# GPIO_Block.net
KiCad netlist of a schematic drawn in EAGLE
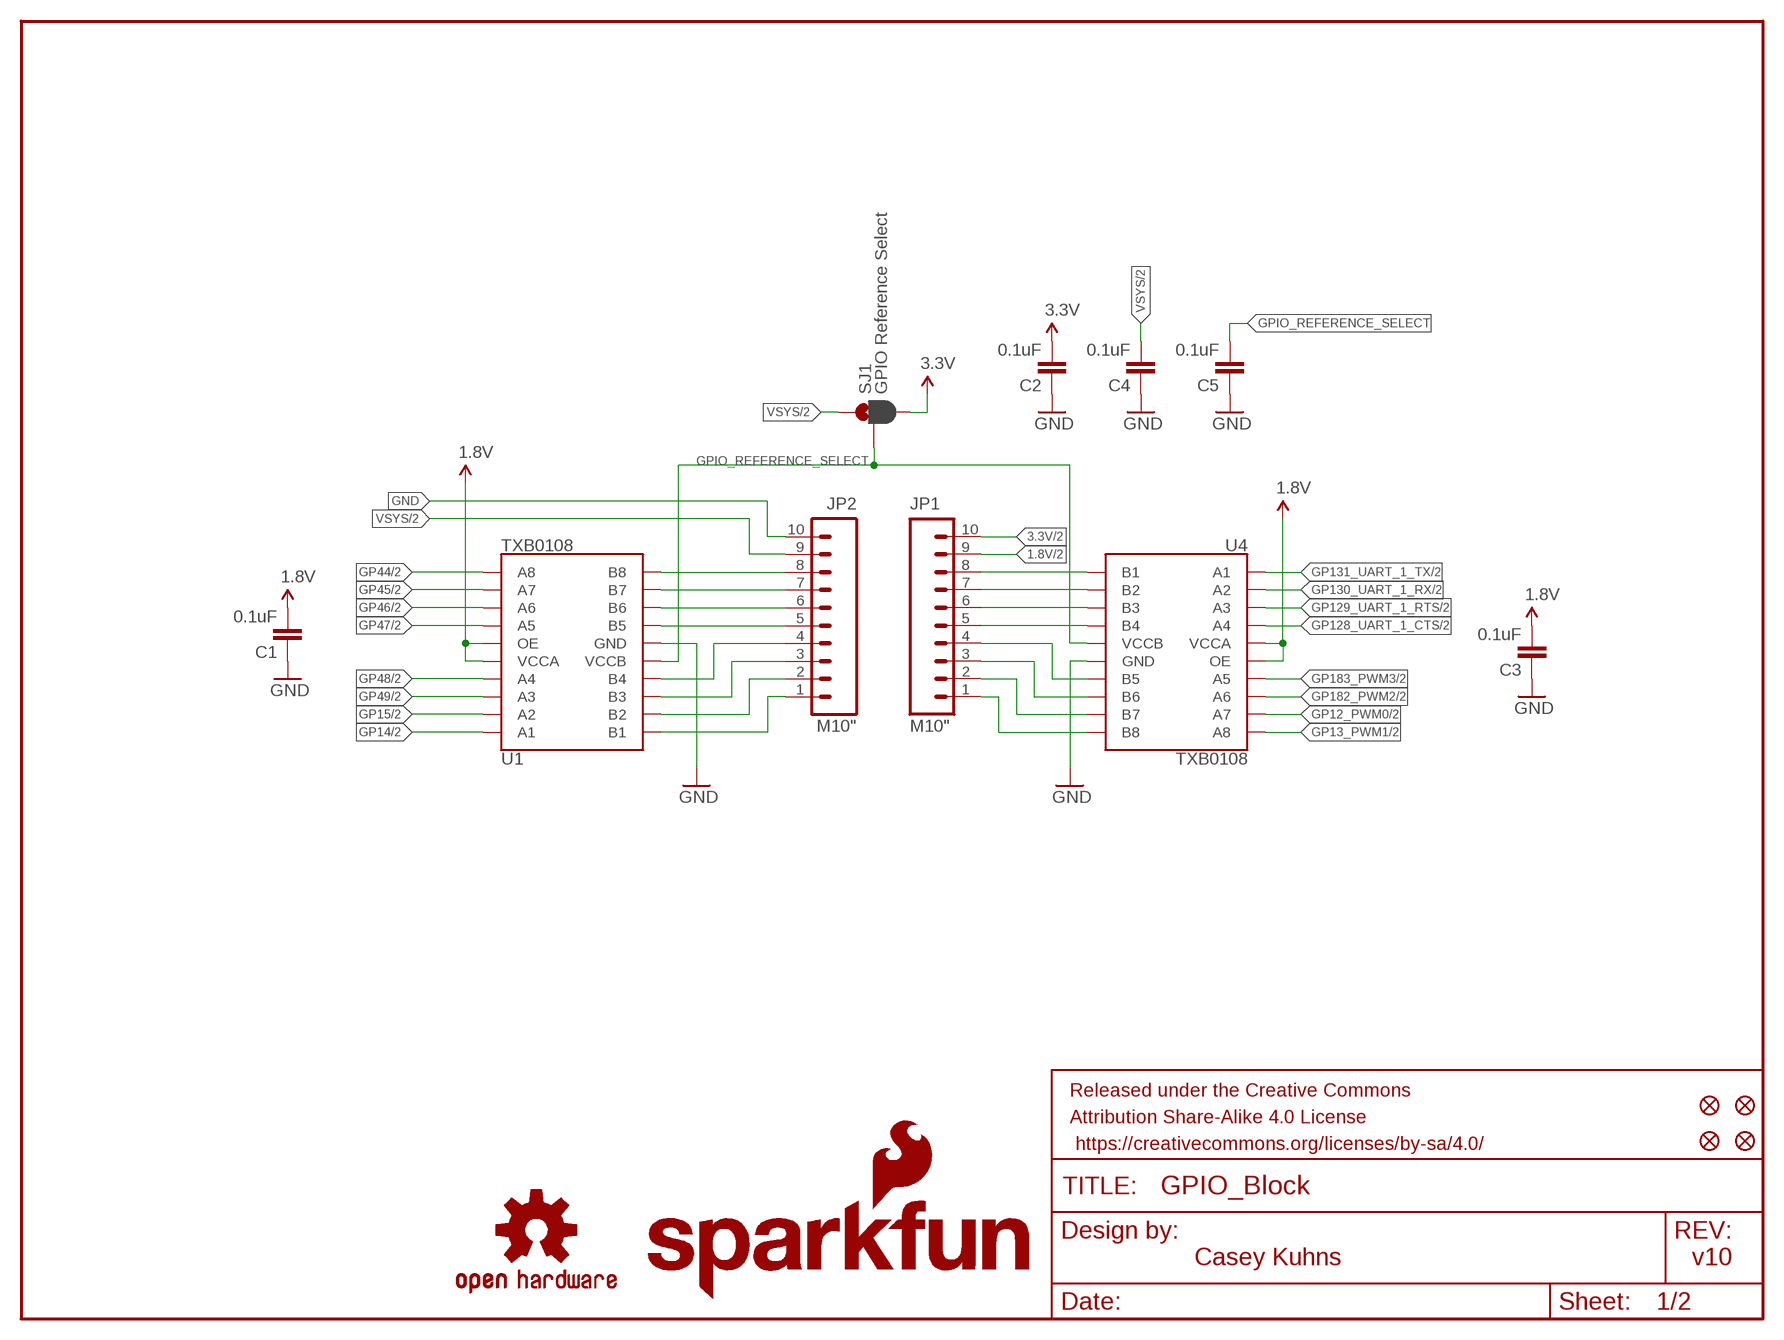
[diagram p0: schematic, sheet 1]
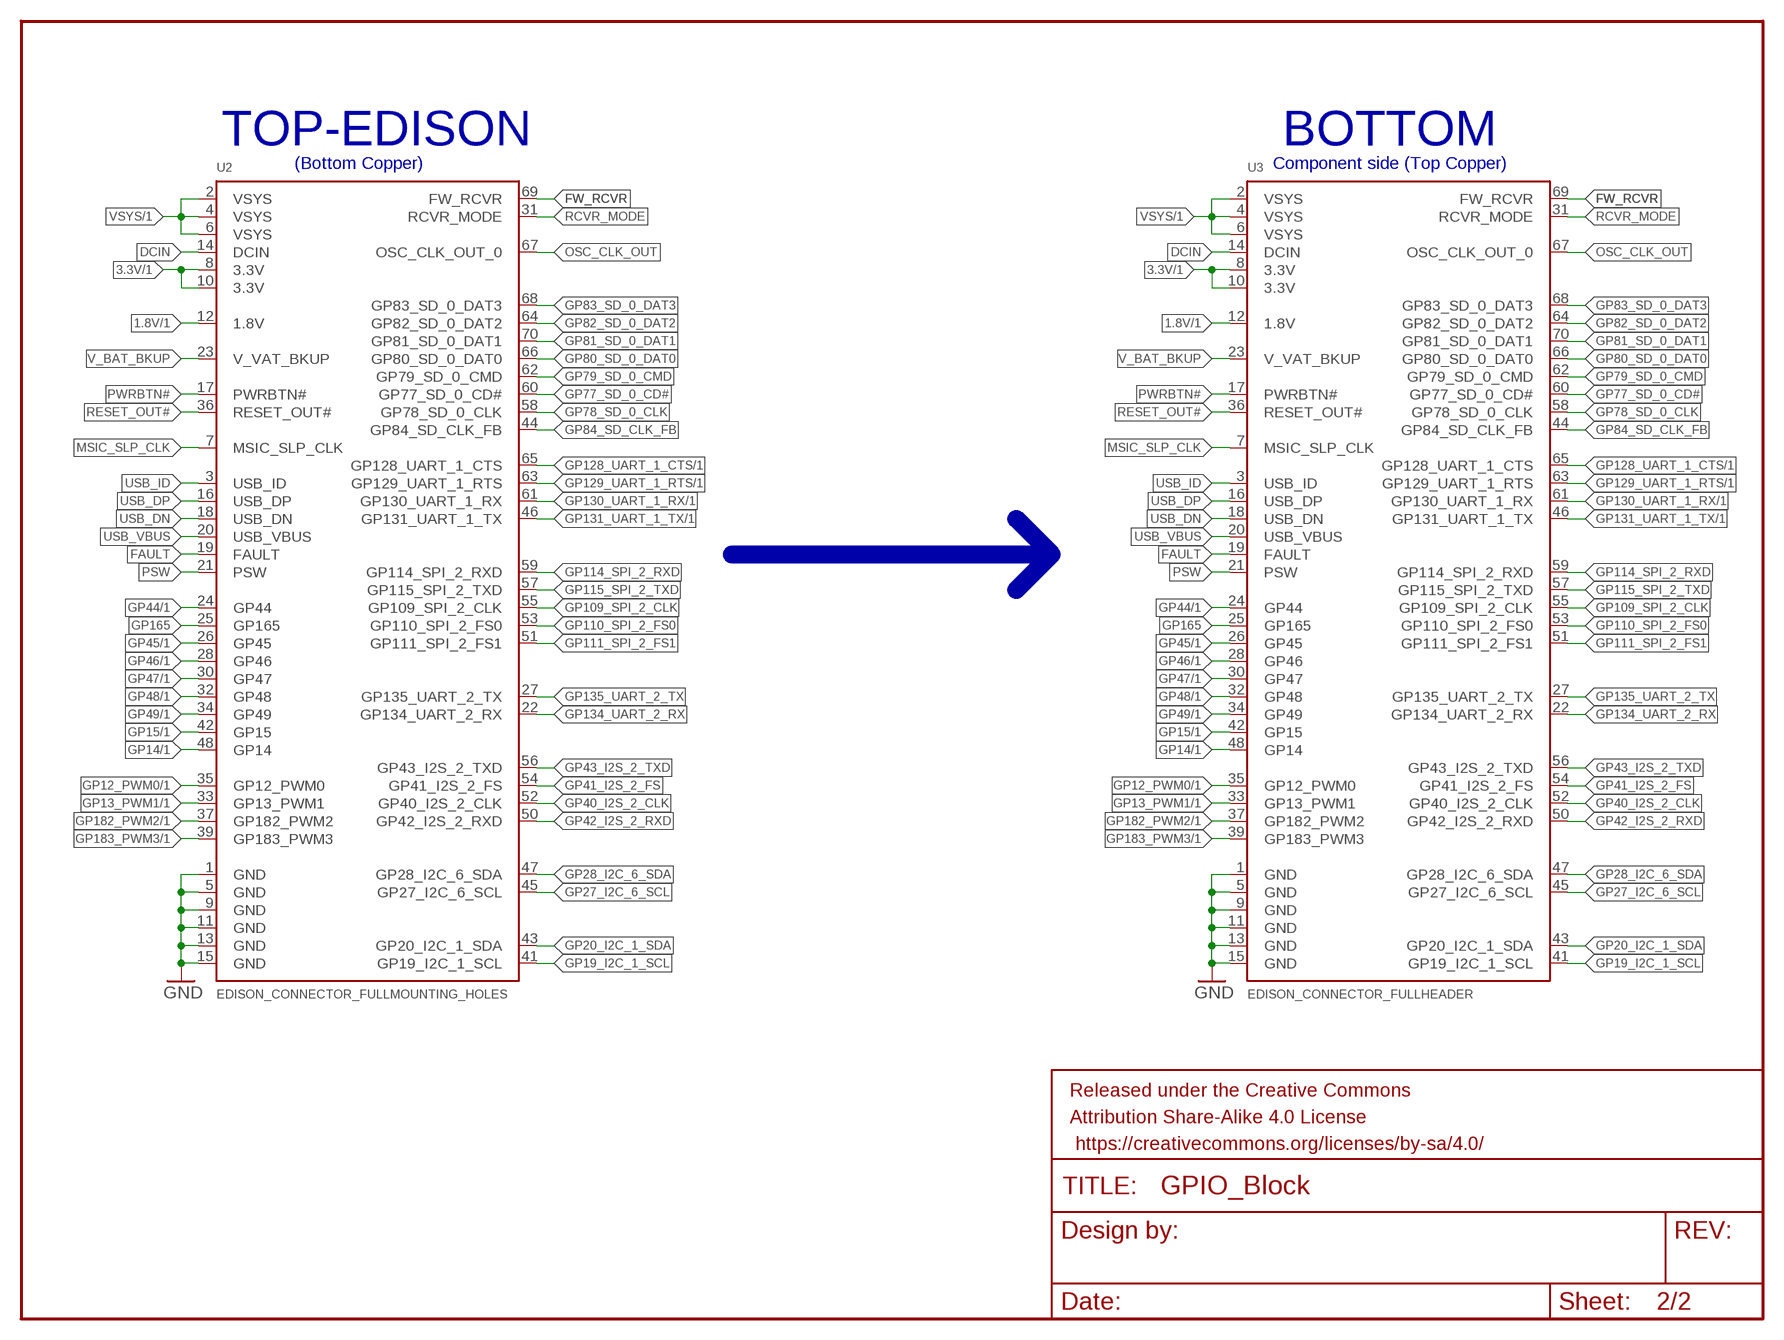
[diagram p1: schematic, sheet 2]

(export (version "E")
  (design (tool "Eeschema 10.0.6"))
  (components
    (comp (ref "C1")
      (value "0.1uF")
      (footprint "eagle-import:0603-CAP")
      (libsource (lib "eagle-import") (part "0.1UF-25V(+80/-20%)(0603)"))
    )
    (comp (ref "C2")
      (value "0.1uF")
      (footprint "eagle-import:0603-CAP")
      (libsource (lib "eagle-import") (part "0.1UF-25V(+80/-20%)(0603)"))
    )
    (comp (ref "C3")
      (value "0.1uF")
      (footprint "eagle-import:0603-CAP")
      (libsource (lib "eagle-import") (part "0.1UF-25V(+80/-20%)(0603)"))
    )
    (comp (ref "C4")
      (value "0.1uF")
      (footprint "eagle-import:0603-CAP")
      (libsource (lib "eagle-import") (part "0.1UF-25V(+80/-20%)(0603)"))
    )
    (comp (ref "C5")
      (value "0.1uF")
      (footprint "eagle-import:0603-CAP")
      (libsource (lib "eagle-import") (part "0.1UF-25V(+80/-20%)(0603)"))
    )
    (comp (ref "FID1")
      (value "FIDUCIAL1X2")
      (footprint "eagle-import:FIDUCIAL-1X2")
      (libsource (lib "eagle-import") (part "FIDUCIAL1X2"))
    )
    (comp (ref "FID2")
      (value "FIDUCIAL1X2")
      (footprint "eagle-import:FIDUCIAL-1X2")
      (libsource (lib "eagle-import") (part "FIDUCIAL1X2"))
    )
    (comp (ref "FID3")
      (value "FIDUCIAL1X2")
      (footprint "eagle-import:FIDUCIAL-1X2")
      (libsource (lib "eagle-import") (part "FIDUCIAL1X2"))
    )
    (comp (ref "FID4")
      (value "FIDUCIAL1X2")
      (footprint "eagle-import:FIDUCIAL-1X2")
      (libsource (lib "eagle-import") (part "FIDUCIAL1X2"))
    )
    (comp (ref "FRAME1")
      (value "FRAME-LETTER")
      (footprint "eagle-import:CREATIVE_COMMONS")
      (libsource (lib "eagle-import") (part "FRAME-LETTER"))
    )
    (comp (ref "JP1")
      (value "M10\"")
      (footprint "eagle-import:1X10")
      (libsource (lib "eagle-import") (part "M10{dblquote}"))
    )
    (comp (ref "JP2")
      (value "M10\"")
      (footprint "eagle-import:1X10")
      (libsource (lib "eagle-import") (part "M10{dblquote}"))
    )
    (comp (ref "LOGO1")
      (value "OSHW-LOGOS")
      (footprint "eagle-import:OSHW-LOGO-S")
      (libsource (lib "eagle-import") (part "OSHW-LOGOS"))
    )
    (comp (ref "LOGO4")
      (value "SFE_LOGO_NAME_FLAME.1_INCH")
      (footprint "eagle-import:SFE_LOGO_NAME_FLAME_.1")
      (libsource (lib "eagle-import") (part "SFE_LOGO_NAME_FLAME.1_INCH"))
    )
    (comp (ref "SJ1")
      (value "GPIO Reference Select")
      (footprint "eagle-import:PAD-JUMPER-3-2OF3_NC_BY_PASTE_YES_SILK_FULL_BOX")
      (libsource (lib "eagle-import") (part "JUMPER-PAD-3-2OF3_NC_BY_PASTE"))
    )
    (comp (ref "U1")
      (value "TXB0108")
      (footprint "eagle-import:UFDFN-20")
      (libsource (lib "eagle-import") (part "TXB0108"))
    )
    (comp (ref "U4")
      (value "TXB0108")
      (footprint "eagle-import:UFDFN-20")
      (libsource (lib "eagle-import") (part "TXB0108"))
    )
    (comp (ref "FRAME2")
      (value "FRAME-LETTER")
      (footprint "eagle-import:CREATIVE_COMMONS")
      (libsource (lib "eagle-import") (part "FRAME-LETTER"))
    )
    (comp (ref "U2")
      (value "EDISON_CONNECTOR_FULLMOUNTING_HOLES")
      (footprint "eagle-import:EDISON_DAUGHTER")
      (libsource (lib "eagle-import") (part "EDISON_CONNECTOR_FULLMOUNTING_HOLES"))
    )
    (comp (ref "U3")
      (value "EDISON_CONNECTOR_FULLHEADER")
      (footprint "eagle-import:DF40C-70DP-0.4(51)")
      (libsource (lib "eagle-import") (part "EDISON_CONNECTOR_FULLHEADER"))
    )
  )
  (nets
    (net (code "1") (name "1.8V") (class "Default")
      (node (ref "C1") (pin "2") (pinfunction "2_2") (pintype "passive"))
      (node (ref "C3") (pin "2") (pinfunction "2_2") (pintype "passive"))
      (node (ref "JP1") (pin "9") (pinfunction "9_9") (pintype "passive"))
      (node (ref "U1") (pin "5") (pinfunction "VCCA_5") (pintype "bidirectional"))
      (node (ref "U1") (pin "6") (pinfunction "OE_6") (pintype "bidirectional"))
      (node (ref "U2") (pin "12") (pinfunction "1.8V_12") (pintype "bidirectional"))
      (node (ref "U3") (pin "12") (pinfunction "1.8V_12") (pintype "bidirectional"))
      (node (ref "U4") (pin "5") (pinfunction "VCCA_5") (pintype "bidirectional"))
      (node (ref "U4") (pin "6") (pinfunction "OE_6") (pintype "bidirectional"))
    )
    (net (code "2") (name "3.3V") (class "Default")
      (node (ref "C2") (pin "2") (pinfunction "2_2") (pintype "passive"))
      (node (ref "JP1") (pin "10") (pinfunction "10_10") (pintype "passive"))
      (node (ref "SJ1") (pin "3") (pinfunction "3_3") (pintype "passive"))
      (node (ref "U2") (pin "10") (pinfunction "3.3V_10") (pintype "bidirectional"))
      (node (ref "U2") (pin "8") (pinfunction "3.3V_8") (pintype "bidirectional"))
      (node (ref "U3") (pin "10") (pinfunction "3.3V_10") (pintype "bidirectional"))
      (node (ref "U3") (pin "8") (pinfunction "3.3V_8") (pintype "bidirectional"))
    )
    (net (code "3") (name "DCIN") (class "Default")
      (node (ref "U2") (pin "14") (pinfunction "DCIN_14") (pintype "bidirectional"))
      (node (ref "U3") (pin "14") (pinfunction "DCIN_14") (pintype "bidirectional"))
    )
    (net (code "4") (name "FAULT") (class "Default")
      (node (ref "U2") (pin "19") (pinfunction "FAULT_19") (pintype "bidirectional"))
      (node (ref "U3") (pin "19") (pinfunction "FAULT_19") (pintype "bidirectional"))
    )
    (net (code "5") (name "FW_RCVR") (class "Default")
      (node (ref "U2") (pin "69") (pinfunction "FW_RCVR_69") (pintype "bidirectional"))
      (node (ref "U3") (pin "69") (pinfunction "FW_RCVR_69") (pintype "bidirectional"))
    )
    (net (code "6") (name "GND") (class "Default")
      (node (ref "C1") (pin "1") (pinfunction "1_1") (pintype "passive"))
      (node (ref "C2") (pin "1") (pinfunction "1_1") (pintype "passive"))
      (node (ref "C3") (pin "1") (pinfunction "1_1") (pintype "passive"))
      (node (ref "C4") (pin "1") (pinfunction "1_1") (pintype "passive"))
      (node (ref "C5") (pin "1") (pinfunction "1_1") (pintype "passive"))
      (node (ref "JP2") (pin "10") (pinfunction "10_10") (pintype "passive"))
      (node (ref "U1") (pin "15") (pinfunction "GND_15") (pintype "bidirectional"))
      (node (ref "U2") (pin "1") (pinfunction "GND_1") (pintype "bidirectional"))
      (node (ref "U2") (pin "11") (pinfunction "GND_11") (pintype "bidirectional"))
      (node (ref "U2") (pin "13") (pinfunction "GND_13") (pintype "bidirectional"))
      (node (ref "U2") (pin "15") (pinfunction "GND_15") (pintype "bidirectional"))
      (node (ref "U2") (pin "5") (pinfunction "GND_5") (pintype "bidirectional"))
      (node (ref "U2") (pin "9") (pinfunction "GND_9") (pintype "bidirectional"))
      (node (ref "U3") (pin "1") (pinfunction "GND_1") (pintype "bidirectional"))
      (node (ref "U3") (pin "11") (pinfunction "GND_11") (pintype "bidirectional"))
      (node (ref "U3") (pin "13") (pinfunction "GND_13") (pintype "bidirectional"))
      (node (ref "U3") (pin "15") (pinfunction "GND_15") (pintype "bidirectional"))
      (node (ref "U3") (pin "5") (pinfunction "GND_5") (pintype "bidirectional"))
      (node (ref "U3") (pin "9") (pinfunction "GND_9") (pintype "bidirectional"))
      (node (ref "U4") (pin "15") (pinfunction "GND_15") (pintype "bidirectional"))
    )
    (net (code "7") (name "GP12_PWM0") (class "Default")
      (node (ref "U2") (pin "35") (pinfunction "GP12_PWM0_35") (pintype "bidirectional"))
      (node (ref "U3") (pin "35") (pinfunction "GP12_PWM0_35") (pintype "bidirectional"))
      (node (ref "U4") (pin "9") (pinfunction "A7_9") (pintype "bidirectional"))
    )
    (net (code "8") (name "GP13_PWM1") (class "Default")
      (node (ref "U2") (pin "33") (pinfunction "GP13_PWM1_33") (pintype "bidirectional"))
      (node (ref "U3") (pin "33") (pinfunction "GP13_PWM1_33") (pintype "bidirectional"))
      (node (ref "U4") (pin "10") (pinfunction "A8_10") (pintype "bidirectional"))
    )
    (net (code "9") (name "GP14") (class "Default")
      (node (ref "U1") (pin "1") (pinfunction "A1_1") (pintype "bidirectional"))
      (node (ref "U2") (pin "48") (pinfunction "GP14_48") (pintype "bidirectional"))
      (node (ref "U3") (pin "48") (pinfunction "GP14_48") (pintype "bidirectional"))
    )
    (net (code "10") (name "GP15") (class "Default")
      (node (ref "U1") (pin "2") (pinfunction "A2_2") (pintype "bidirectional"))
      (node (ref "U2") (pin "42") (pinfunction "GP15_42") (pintype "bidirectional"))
      (node (ref "U3") (pin "42") (pinfunction "GP15_42") (pintype "bidirectional"))
    )
    (net (code "11") (name "GP19_I2C_1_SCL") (class "Default")
      (node (ref "U2") (pin "41") (pinfunction "GP19_I2C_1_SCL_41") (pintype "bidirectional"))
      (node (ref "U3") (pin "41") (pinfunction "GP19_I2C_1_SCL_41") (pintype "bidirectional"))
    )
    (net (code "12") (name "GP20_I2C_1_SDA") (class "Default")
      (node (ref "U2") (pin "43") (pinfunction "GP20_I2C_1_SDA_43") (pintype "bidirectional"))
      (node (ref "U3") (pin "43") (pinfunction "GP20_I2C_1_SDA_43") (pintype "bidirectional"))
    )
    (net (code "13") (name "GP27_I2C_6_SCL") (class "Default")
      (node (ref "U2") (pin "45") (pinfunction "GP27_I2C_6_SCL_45") (pintype "bidirectional"))
      (node (ref "U3") (pin "45") (pinfunction "GP27_I2C_6_SCL_45") (pintype "bidirectional"))
    )
    (net (code "14") (name "GP28_I2C_6_SDA") (class "Default")
      (node (ref "U2") (pin "47") (pinfunction "GP28_I2C_6_SDA_47") (pintype "bidirectional"))
      (node (ref "U3") (pin "47") (pinfunction "GP28_I2C_6_SDA_47") (pintype "bidirectional"))
    )
    (net (code "15") (name "GP40_I2S_2_CLK") (class "Default")
      (node (ref "U2") (pin "52") (pinfunction "GP40_I2S_2_CLK_52") (pintype "bidirectional"))
      (node (ref "U3") (pin "52") (pinfunction "GP40_I2S_2_CLK_52") (pintype "bidirectional"))
    )
    (net (code "16") (name "GP41_I2S_2_FS") (class "Default")
      (node (ref "U2") (pin "54") (pinfunction "GP41_I2S_2_FS_54") (pintype "bidirectional"))
      (node (ref "U3") (pin "54") (pinfunction "GP41_I2S_2_FS_54") (pintype "bidirectional"))
    )
    (net (code "17") (name "GP42_I2S_2_RXD") (class "Default")
      (node (ref "U2") (pin "50") (pinfunction "GP42_I2S_2_RXD_50") (pintype "bidirectional"))
      (node (ref "U3") (pin "50") (pinfunction "GP42_I2S_2_RXD_50") (pintype "bidirectional"))
    )
    (net (code "18") (name "GP43_I2S_2_TXD") (class "Default")
      (node (ref "U2") (pin "56") (pinfunction "GP43_I2S_2_TXD_56") (pintype "bidirectional"))
      (node (ref "U3") (pin "56") (pinfunction "GP43_I2S_2_TXD_56") (pintype "bidirectional"))
    )
    (net (code "19") (name "GP44") (class "Default")
      (node (ref "U1") (pin "10") (pinfunction "A8_10") (pintype "bidirectional"))
      (node (ref "U2") (pin "24") (pinfunction "GP44_24") (pintype "bidirectional"))
      (node (ref "U3") (pin "24") (pinfunction "GP44_24") (pintype "bidirectional"))
    )
    (net (code "20") (name "GP45") (class "Default")
      (node (ref "U1") (pin "9") (pinfunction "A7_9") (pintype "bidirectional"))
      (node (ref "U2") (pin "26") (pinfunction "GP45_26") (pintype "bidirectional"))
      (node (ref "U3") (pin "26") (pinfunction "GP45_26") (pintype "bidirectional"))
    )
    (net (code "21") (name "GP46") (class "Default")
      (node (ref "U1") (pin "8") (pinfunction "A6_8") (pintype "bidirectional"))
      (node (ref "U2") (pin "28") (pinfunction "GP46_28") (pintype "bidirectional"))
      (node (ref "U3") (pin "28") (pinfunction "GP46_28") (pintype "bidirectional"))
    )
    (net (code "22") (name "GP47") (class "Default")
      (node (ref "U1") (pin "7") (pinfunction "A5_7") (pintype "bidirectional"))
      (node (ref "U2") (pin "30") (pinfunction "GP47_30") (pintype "bidirectional"))
      (node (ref "U3") (pin "30") (pinfunction "GP47_30") (pintype "bidirectional"))
    )
    (net (code "23") (name "GP48") (class "Default")
      (node (ref "U1") (pin "4") (pinfunction "A4_4") (pintype "bidirectional"))
      (node (ref "U2") (pin "32") (pinfunction "GP48_32") (pintype "bidirectional"))
      (node (ref "U3") (pin "32") (pinfunction "GP48_32") (pintype "bidirectional"))
    )
    (net (code "24") (name "GP49") (class "Default")
      (node (ref "U1") (pin "3") (pinfunction "A3_3") (pintype "bidirectional"))
      (node (ref "U2") (pin "34") (pinfunction "GP49_34") (pintype "bidirectional"))
      (node (ref "U3") (pin "34") (pinfunction "GP49_34") (pintype "bidirectional"))
    )
    (net (code "25") (name "GP77_SD_0_CD#") (class "Default")
      (node (ref "U2") (pin "60") (pinfunction "GP77_SD_0_CD#_60") (pintype "bidirectional"))
      (node (ref "U3") (pin "60") (pinfunction "GP77_SD_0_CD#_60") (pintype "bidirectional"))
    )
    (net (code "26") (name "GP78_SD_0_CLK") (class "Default")
      (node (ref "U2") (pin "58") (pinfunction "GP78_SD_0_CLK_58") (pintype "bidirectional"))
      (node (ref "U3") (pin "58") (pinfunction "GP78_SD_0_CLK_58") (pintype "bidirectional"))
    )
    (net (code "27") (name "GP79_SD_0_CMD") (class "Default")
      (node (ref "U2") (pin "62") (pinfunction "GP79_SD_0_CMD_62") (pintype "bidirectional"))
      (node (ref "U3") (pin "62") (pinfunction "GP79_SD_0_CMD_62") (pintype "bidirectional"))
    )
    (net (code "28") (name "GP80_SD_0_DAT0") (class "Default")
      (node (ref "U2") (pin "66") (pinfunction "GP80_SD_0_DAT0_66") (pintype "bidirectional"))
      (node (ref "U3") (pin "66") (pinfunction "GP80_SD_0_DAT0_66") (pintype "bidirectional"))
    )
    (net (code "29") (name "GP81_SD_0_DAT1") (class "Default")
      (node (ref "U2") (pin "70") (pinfunction "GP81_SD_0_DAT1_70") (pintype "bidirectional"))
      (node (ref "U3") (pin "70") (pinfunction "GP81_SD_0_DAT1_70") (pintype "bidirectional"))
    )
    (net (code "30") (name "GP82_SD_0_DAT2") (class "Default")
      (node (ref "U2") (pin "64") (pinfunction "GP82_SD_0_DAT2_64") (pintype "bidirectional"))
      (node (ref "U3") (pin "64") (pinfunction "GP82_SD_0_DAT2_64") (pintype "bidirectional"))
    )
    (net (code "31") (name "GP83_SD_0_DAT3") (class "Default")
      (node (ref "U2") (pin "68") (pinfunction "GP83_SD_0_DAT3_68") (pintype "bidirectional"))
      (node (ref "U3") (pin "68") (pinfunction "GP83_SD_0_DAT3_68") (pintype "bidirectional"))
    )
    (net (code "32") (name "GP84_SD_CLK_FB") (class "Default")
      (node (ref "U2") (pin "44") (pinfunction "GP84_SD_CLK_FB_44") (pintype "bidirectional"))
      (node (ref "U3") (pin "44") (pinfunction "GP84_SD_CLK_FB_44") (pintype "bidirectional"))
    )
    (net (code "33") (name "GP109_SPI_2_CLK") (class "Default")
      (node (ref "U2") (pin "55") (pinfunction "GP109_SPI_2_CLK_55") (pintype "bidirectional"))
      (node (ref "U3") (pin "55") (pinfunction "GP109_SPI_2_CLK_55") (pintype "bidirectional"))
    )
    (net (code "34") (name "GP110_SPI_2_FS0") (class "Default")
      (node (ref "U2") (pin "53") (pinfunction "GP110_SPI_2_FS0_53") (pintype "bidirectional"))
      (node (ref "U3") (pin "53") (pinfunction "GP110_SPI_2_FS0_53") (pintype "bidirectional"))
    )
    (net (code "35") (name "GP111_SPI_2_FS1") (class "Default")
      (node (ref "U2") (pin "51") (pinfunction "GP111_SPI_2_FS1_51") (pintype "bidirectional"))
      (node (ref "U3") (pin "51") (pinfunction "GP111_SPI_2_FS1_51") (pintype "bidirectional"))
    )
    (net (code "36") (name "GP114_SPI_2_RXD") (class "Default")
      (node (ref "U2") (pin "59") (pinfunction "GP114_SPI_2_RXD_59") (pintype "bidirectional"))
      (node (ref "U3") (pin "59") (pinfunction "GP114_SPI_2_RXD_59") (pintype "bidirectional"))
    )
    (net (code "37") (name "GP115_SPI_2_TXD") (class "Default")
      (node (ref "U2") (pin "57") (pinfunction "GP115_SPI_2_TXD_57") (pintype "bidirectional"))
      (node (ref "U3") (pin "57") (pinfunction "GP115_SPI_2_TXD_57") (pintype "bidirectional"))
    )
    (net (code "38") (name "GP128_UART_1_CTS") (class "Default")
      (node (ref "U2") (pin "65") (pinfunction "GP128_UART_1_CTS_65") (pintype "bidirectional"))
      (node (ref "U3") (pin "65") (pinfunction "GP128_UART_1_CTS_65") (pintype "bidirectional"))
      (node (ref "U4") (pin "4") (pinfunction "A4_4") (pintype "bidirectional"))
    )
    (net (code "39") (name "GP129_UART_1_RTS") (class "Default")
      (node (ref "U2") (pin "63") (pinfunction "GP129_UART_1_RTS_63") (pintype "bidirectional"))
      (node (ref "U3") (pin "63") (pinfunction "GP129_UART_1_RTS_63") (pintype "bidirectional"))
      (node (ref "U4") (pin "3") (pinfunction "A3_3") (pintype "bidirectional"))
    )
    (net (code "40") (name "GP130_UART_1_RX") (class "Default")
      (node (ref "U2") (pin "61") (pinfunction "GP130_UART_1_RX_61") (pintype "bidirectional"))
      (node (ref "U3") (pin "61") (pinfunction "GP130_UART_1_RX_61") (pintype "bidirectional"))
      (node (ref "U4") (pin "2") (pinfunction "A2_2") (pintype "bidirectional"))
    )
    (net (code "41") (name "GP131_UART_1_TX") (class "Default")
      (node (ref "U2") (pin "46") (pinfunction "GP131_UART_1_TX_46") (pintype "bidirectional"))
      (node (ref "U3") (pin "46") (pinfunction "GP131_UART_1_TX_46") (pintype "bidirectional"))
      (node (ref "U4") (pin "1") (pinfunction "A1_1") (pintype "bidirectional"))
    )
    (net (code "42") (name "GP134_UART_2_RX") (class "Default")
      (node (ref "U2") (pin "22") (pinfunction "GP134_UART_2_RX_22") (pintype "bidirectional"))
      (node (ref "U3") (pin "22") (pinfunction "GP134_UART_2_RX_22") (pintype "bidirectional"))
    )
    (net (code "43") (name "GP135_UART_2_TX") (class "Default")
      (node (ref "U2") (pin "27") (pinfunction "GP135_UART_2_TX_27") (pintype "bidirectional"))
      (node (ref "U3") (pin "27") (pinfunction "GP135_UART_2_TX_27") (pintype "bidirectional"))
    )
    (net (code "44") (name "GP165") (class "Default")
      (node (ref "U2") (pin "25") (pinfunction "GP165_25") (pintype "bidirectional"))
      (node (ref "U3") (pin "25") (pinfunction "GP165_25") (pintype "bidirectional"))
    )
    (net (code "45") (name "GP182_PWM2") (class "Default")
      (node (ref "U2") (pin "37") (pinfunction "GP182_PWM2_37") (pintype "bidirectional"))
      (node (ref "U3") (pin "37") (pinfunction "GP182_PWM2_37") (pintype "bidirectional"))
      (node (ref "U4") (pin "8") (pinfunction "A6_8") (pintype "bidirectional"))
    )
    (net (code "46") (name "GP183_PWM3") (class "Default")
      (node (ref "U2") (pin "39") (pinfunction "GP183_PWM3_39") (pintype "bidirectional"))
      (node (ref "U3") (pin "39") (pinfunction "GP183_PWM3_39") (pintype "bidirectional"))
      (node (ref "U4") (pin "7") (pinfunction "A5_7") (pintype "bidirectional"))
    )
    (net (code "47") (name "GPIO_REFERENCE_SELECT") (class "Default")
      (node (ref "C5") (pin "2") (pinfunction "2_2") (pintype "passive"))
      (node (ref "SJ1") (pin "2") (pinfunction "2_2") (pintype "passive"))
      (node (ref "U1") (pin "16") (pinfunction "VCCB_16") (pintype "bidirectional"))
      (node (ref "U4") (pin "16") (pinfunction "VCCB_16") (pintype "bidirectional"))
    )
    (net (code "48") (name "MSIC_SLP_CLK") (class "Default")
      (node (ref "U2") (pin "7") (pinfunction "MSIC_SLP_CLK_7") (pintype "bidirectional"))
      (node (ref "U3") (pin "7") (pinfunction "MSIC_SLP_CLK_7") (pintype "bidirectional"))
    )
    (net (code "49") (name "Net-(U1-B1)") (class "Default")
      (node (ref "JP2") (pin "1") (pinfunction "1_1") (pintype "passive"))
      (node (ref "U1") (pin "20") (pinfunction "B1_20") (pintype "bidirectional"))
    )
    (net (code "50") (name "Net-(U1-B2)") (class "Default")
      (node (ref "JP2") (pin "2") (pinfunction "2_2") (pintype "passive"))
      (node (ref "U1") (pin "19") (pinfunction "B2_19") (pintype "bidirectional"))
    )
    (net (code "51") (name "Net-(U1-B3)") (class "Default")
      (node (ref "JP2") (pin "3") (pinfunction "3_3") (pintype "passive"))
      (node (ref "U1") (pin "18") (pinfunction "B3_18") (pintype "bidirectional"))
    )
    (net (code "52") (name "Net-(U1-B4)") (class "Default")
      (node (ref "JP2") (pin "4") (pinfunction "4_4") (pintype "passive"))
      (node (ref "U1") (pin "17") (pinfunction "B4_17") (pintype "bidirectional"))
    )
    (net (code "53") (name "Net-(U1-B5)") (class "Default")
      (node (ref "JP2") (pin "5") (pinfunction "5_5") (pintype "passive"))
      (node (ref "U1") (pin "14") (pinfunction "B5_14") (pintype "bidirectional"))
    )
    (net (code "54") (name "Net-(U1-B6)") (class "Default")
      (node (ref "JP2") (pin "6") (pinfunction "6_6") (pintype "passive"))
      (node (ref "U1") (pin "13") (pinfunction "B6_13") (pintype "bidirectional"))
    )
    (net (code "55") (name "Net-(U1-B7)") (class "Default")
      (node (ref "JP2") (pin "7") (pinfunction "7_7") (pintype "passive"))
      (node (ref "U1") (pin "12") (pinfunction "B7_12") (pintype "bidirectional"))
    )
    (net (code "56") (name "Net-(U1-B8)") (class "Default")
      (node (ref "JP2") (pin "8") (pinfunction "8_8") (pintype "passive"))
      (node (ref "U1") (pin "11") (pinfunction "B8_11") (pintype "bidirectional"))
    )
    (net (code "57") (name "Net-(U4-B1)") (class "Default")
      (node (ref "JP1") (pin "8") (pinfunction "8_8") (pintype "passive"))
      (node (ref "U4") (pin "20") (pinfunction "B1_20") (pintype "bidirectional"))
    )
    (net (code "58") (name "Net-(U4-B2)") (class "Default")
      (node (ref "JP1") (pin "7") (pinfunction "7_7") (pintype "passive"))
      (node (ref "U4") (pin "19") (pinfunction "B2_19") (pintype "bidirectional"))
    )
    (net (code "59") (name "Net-(U4-B3)") (class "Default")
      (node (ref "JP1") (pin "6") (pinfunction "6_6") (pintype "passive"))
      (node (ref "U4") (pin "18") (pinfunction "B3_18") (pintype "bidirectional"))
    )
    (net (code "60") (name "Net-(U4-B4)") (class "Default")
      (node (ref "JP1") (pin "5") (pinfunction "5_5") (pintype "passive"))
      (node (ref "U4") (pin "17") (pinfunction "B4_17") (pintype "bidirectional"))
    )
    (net (code "61") (name "Net-(U4-B5)") (class "Default")
      (node (ref "JP1") (pin "4") (pinfunction "4_4") (pintype "passive"))
      (node (ref "U4") (pin "14") (pinfunction "B5_14") (pintype "bidirectional"))
    )
    (net (code "62") (name "Net-(U4-B6)") (class "Default")
      (node (ref "JP1") (pin "3") (pinfunction "3_3") (pintype "passive"))
      (node (ref "U4") (pin "13") (pinfunction "B6_13") (pintype "bidirectional"))
    )
    (net (code "63") (name "Net-(U4-B7)") (class "Default")
      (node (ref "JP1") (pin "2") (pinfunction "2_2") (pintype "passive"))
      (node (ref "U4") (pin "12") (pinfunction "B7_12") (pintype "bidirectional"))
    )
    (net (code "64") (name "Net-(U4-B8)") (class "Default")
      (node (ref "JP1") (pin "1") (pinfunction "1_1") (pintype "passive"))
      (node (ref "U4") (pin "11") (pinfunction "B8_11") (pintype "bidirectional"))
    )
    (net (code "65") (name "OSC_CLK_OUT") (class "Default")
      (node (ref "U2") (pin "67") (pinfunction "OSC_CLK_OUT_0_67") (pintype "bidirectional"))
      (node (ref "U3") (pin "67") (pinfunction "OSC_CLK_OUT_0_67") (pintype "bidirectional"))
    )
    (net (code "66") (name "PSW") (class "Default")
      (node (ref "U2") (pin "21") (pinfunction "PSW_21") (pintype "bidirectional"))
      (node (ref "U3") (pin "21") (pinfunction "PSW_21") (pintype "bidirectional"))
    )
    (net (code "67") (name "PWRBTN#") (class "Default")
      (node (ref "U2") (pin "17") (pinfunction "PWRBTN#_17") (pintype "bidirectional"))
      (node (ref "U3") (pin "17") (pinfunction "PWRBTN#_17") (pintype "bidirectional"))
    )
    (net (code "68") (name "RCVR_MODE") (class "Default")
      (node (ref "U2") (pin "31") (pinfunction "RCVR_MODE_31") (pintype "bidirectional"))
      (node (ref "U3") (pin "31") (pinfunction "RCVR_MODE_31") (pintype "bidirectional"))
    )
    (net (code "69") (name "RESET_OUT#") (class "Default")
      (node (ref "U2") (pin "36") (pinfunction "RESET_OUT#_36") (pintype "bidirectional"))
      (node (ref "U3") (pin "36") (pinfunction "RESET_OUT#_36") (pintype "bidirectional"))
    )
    (net (code "70") (name "USB_DN") (class "Default")
      (node (ref "U2") (pin "18") (pinfunction "USB_DN_18") (pintype "bidirectional"))
      (node (ref "U3") (pin "18") (pinfunction "USB_DN_18") (pintype "bidirectional"))
    )
    (net (code "71") (name "USB_DP") (class "Default")
      (node (ref "U2") (pin "16") (pinfunction "USB_DP_16") (pintype "bidirectional"))
      (node (ref "U3") (pin "16") (pinfunction "USB_DP_16") (pintype "bidirectional"))
    )
    (net (code "72") (name "USB_ID") (class "Default")
      (node (ref "U2") (pin "3") (pinfunction "USB_ID_3") (pintype "bidirectional"))
      (node (ref "U3") (pin "3") (pinfunction "USB_ID_3") (pintype "bidirectional"))
    )
    (net (code "73") (name "USB_VBUS") (class "Default")
      (node (ref "U2") (pin "20") (pinfunction "USB_VBUS_20") (pintype "bidirectional"))
      (node (ref "U3") (pin "20") (pinfunction "USB_VBUS_20") (pintype "bidirectional"))
    )
    (net (code "74") (name "VSYS") (class "Default")
      (node (ref "C4") (pin "2") (pinfunction "2_2") (pintype "passive"))
      (node (ref "JP2") (pin "9") (pinfunction "9_9") (pintype "passive"))
      (node (ref "SJ1") (pin "1") (pinfunction "1_1") (pintype "passive"))
      (node (ref "U2") (pin "2") (pinfunction "VSYS_2") (pintype "bidirectional"))
      (node (ref "U2") (pin "4") (pinfunction "VSYS_4") (pintype "bidirectional"))
      (node (ref "U2") (pin "6") (pinfunction "VSYS_6") (pintype "bidirectional"))
      (node (ref "U3") (pin "2") (pinfunction "VSYS_2") (pintype "bidirectional"))
      (node (ref "U3") (pin "4") (pinfunction "VSYS_4") (pintype "bidirectional"))
      (node (ref "U3") (pin "6") (pinfunction "VSYS_6") (pintype "bidirectional"))
    )
    (net (code "75") (name "V_BAT_BKUP") (class "Default")
      (node (ref "U2") (pin "23") (pinfunction "V_VAT_BKUP_23") (pintype "bidirectional"))
      (node (ref "U3") (pin "23") (pinfunction "V_VAT_BKUP_23") (pintype "bidirectional"))
    )
  )
)
